# Photogate.net
KiCad netlist of a schematic drawn in Altium Designer
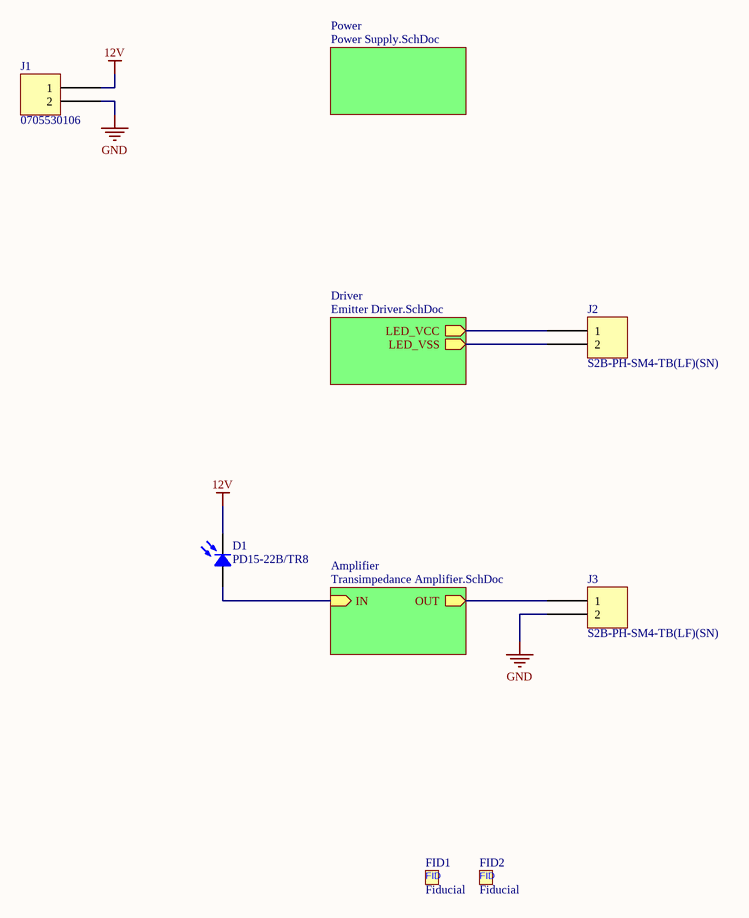
[diagram p0: Photogate.SchDoc]

(export (version "E")
  (design (tool "Eeschema 10.0.6"))
  (components
    (comp (ref "D1")
      (value "PD15-22B/TR8")
      (footprint "Everlight PD15-22")
      (description "SENSOR PHOTODIODE 940NM 4SMD")
      (fields (field (name "MANUFACTURER") "Everlight Electronics Co Ltd"))
      (libsource (lib "Celestial Altium Library - altium_library") (part "PHOTODIODE"))
    )
    (comp (ref "FID1") (value "Fiducial") (footprint "Fiducial") (libsource (lib "Useful") (part "Fiducial")))
    (comp (ref "FID2") (value "Fiducial") (footprint "Fiducial") (libsource (lib "Useful") (part "Fiducial")))
    (comp (ref "J1")
      (value "0705530106")
      (footprint "MOLEX SDA-70553-2PIN")
      (description "CONN HEADER R/A 2POS 2.54MM")
      (fields (field (name "MANUFACTURER") "Molex"))
      (libsource (lib "") (part "2 Pin_1"))
    )
    (comp (ref "J2")
      (value "S2B-PH-SM4-TB(LF)(SN)")
      (footprint "JST S2B-PH-SM4-TB")
      (description "CONN HEADER SMD R/A 2POS 2MM")
      (fields (field (name "MANUFACTURER") "JST Sales America Inc."))
      (libsource (lib "Celestial Altium Library - altium_library") (part "2 Pin"))
    )
    (comp (ref "J3")
      (value "S2B-PH-SM4-TB(LF)(SN)")
      (footprint "JST S2B-PH-SM4-TB")
      (description "CONN HEADER SMD R/A 2POS 2MM")
      (fields (field (name "MANUFACTURER") "JST Sales America Inc."))
      (libsource (lib "Celestial Altium Library - altium_library") (part "2 Pin"))
    )
  )
  (nets
    (net (code "1") (name "/IN") (class "Default")
      (node (ref "D1") (pin "1") (pinfunction "1_1") (pintype "passive"))
    )
    (net (code "2") (name "/LED_VCC") (class "Default")
      (node (ref "J2") (pin "1") (pinfunction "1_1") (pintype "passive"))
    )
    (net (code "3") (name "/LED_VSS") (class "Default")
      (node (ref "J2") (pin "2") (pinfunction "2_2") (pintype "passive"))
    )
    (net (code "4") (name "/OUT") (class "Default")
      (node (ref "J3") (pin "1") (pinfunction "1_1") (pintype "passive"))
    )
    (net (code "5") (name "12V") (class "Default")
      (node (ref "D1") (pin "2") (pinfunction "2_2") (pintype "passive"))
      (node (ref "J1") (pin "1") (pinfunction "1_1") (pintype "passive"))
    )
    (net (code "6") (name "GND") (class "Default")
      (node (ref "J1") (pin "2") (pinfunction "2_2") (pintype "passive"))
      (node (ref "J3") (pin "2") (pinfunction "2_2") (pintype "passive"))
    )
  )
)
